# Shutdown_2019_v1_1_TractionCtl.net
KiCad netlist of a schematic drawn in Altium Designer
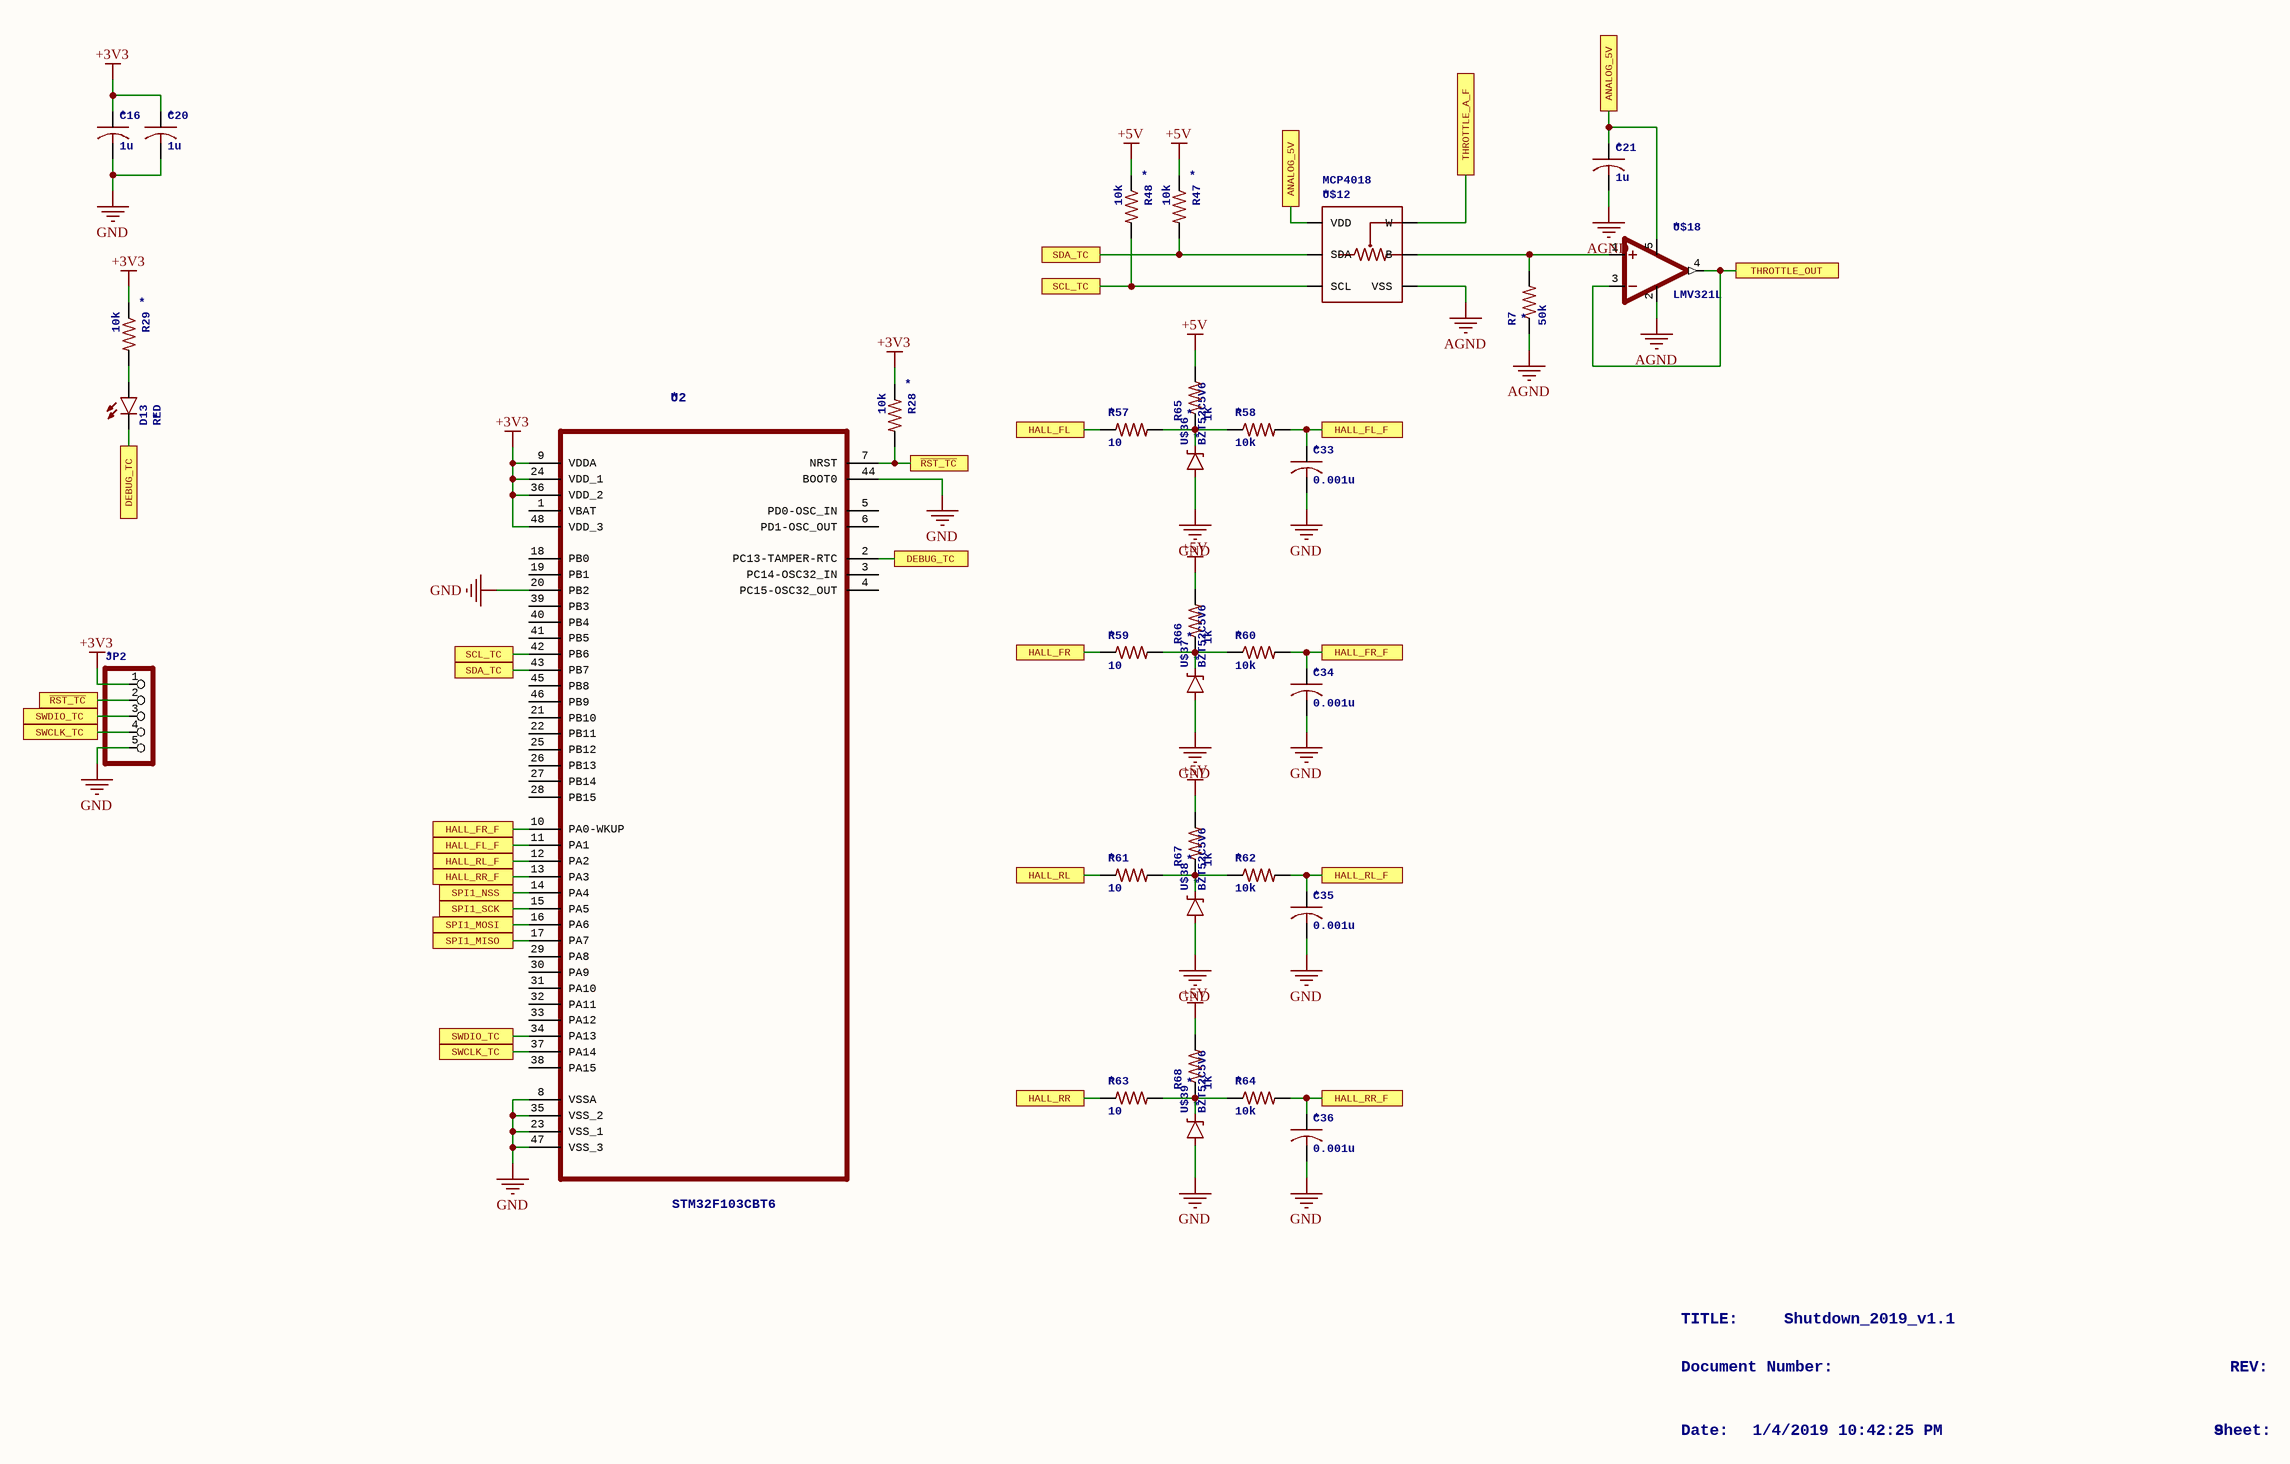
[diagram p0: Shutdown_2019_v1.1_TractionCtl.SchDoc]

(export (version "E")
  (design (tool "Eeschema 10.0.6"))
  (components
    (comp (ref "C16")
      (value "1u")
      (footprint "C0805")
      (description "CAPACITOR, American symbol")
      (fields (field (name "NAME") "*"))
      (libsource (lib "rcl") (part "C-USC0805"))
    )
    (comp (ref "C20")
      (value "1u")
      (footprint "C0805")
      (description "CAPACITOR, American symbol")
      (fields (field (name "NAME") "*"))
      (libsource (lib "rcl") (part "C-USC0805"))
    )
    (comp (ref "C21")
      (value "1u")
      (footprint "C0603")
      (description "CAPACITOR, American symbol")
      (fields (field (name "NAME") "*"))
      (libsource (lib "rcl") (part "C-USC0603"))
    )
    (comp (ref "C33")
      (value "0.001u")
      (footprint "C0805")
      (description "CAPACITOR, American symbol")
      (fields (field (name "NAME") "*"))
      (libsource (lib "rcl") (part "C-USC0805"))
    )
    (comp (ref "C34")
      (value "0.001u")
      (footprint "C0805")
      (description "CAPACITOR, American symbol")
      (fields (field (name "NAME") "*"))
      (libsource (lib "rcl") (part "C-USC0805"))
    )
    (comp (ref "C35")
      (value "0.001u")
      (footprint "C0805")
      (description "CAPACITOR, American symbol")
      (fields (field (name "NAME") "*"))
      (libsource (lib "rcl") (part "C-USC0805"))
    )
    (comp (ref "C36")
      (value "0.001u")
      (footprint "C0805")
      (description "CAPACITOR, American symbol")
      (fields (field (name "NAME") "*"))
      (libsource (lib "rcl") (part "C-USC0805"))
    )
    (comp (ref "D13")
      (value "RED")
      (footprint "LED-0603")
      (fields (field (name "NAME") "*"))
      (libsource (lib "SparkFun-LED") (part "LED-RED0603"))
    )
    (comp (ref "JP2")
      (value "PINHD-1X5")
      (footprint "1X05")
      (description "PIN HEADER")
      (fields (field (name "NAME") "*") (field (name "LIBRARYNAME") "Headers_IFE"))
      (libsource (lib "Headers_IFE") (part "PINHD-1X5"))
    )
    (comp (ref "R7")
      (value "50k")
      (footprint "R0603")
      (description "RESISTOR, American symbol")
      (fields (field (name "NAME") "*"))
      (libsource (lib "rcl") (part "R-US_R0603"))
    )
    (comp (ref "R28")
      (value "10k")
      (footprint "R0603")
      (description "RESISTOR, American symbol")
      (fields (field (name "NAME") "*"))
      (libsource (lib "rcl") (part "R-US_R0603"))
    )
    (comp (ref "R29")
      (value "10k")
      (footprint "R0603")
      (description "RESISTOR, American symbol")
      (fields (field (name "NAME") "*"))
      (libsource (lib "rcl") (part "R-US_R0603"))
    )
    (comp (ref "R47")
      (value "10k")
      (footprint "R0603")
      (description "RESISTOR, American symbol")
      (fields (field (name "NAME") "*"))
      (libsource (lib "rcl") (part "R-US_R0603"))
    )
    (comp (ref "R48")
      (value "10k")
      (footprint "R0603")
      (description "RESISTOR, American symbol")
      (fields (field (name "NAME") "*"))
      (libsource (lib "rcl") (part "R-US_R0603"))
    )
    (comp (ref "R57")
      (value "10")
      (footprint "R0603")
      (description "RESISTOR, American symbol")
      (fields (field (name "NAME") "*"))
      (libsource (lib "rcl") (part "R-US_R0603"))
    )
    (comp (ref "R58")
      (value "10k")
      (footprint "R0603")
      (description "RESISTOR, American symbol")
      (fields (field (name "NAME") "*"))
      (libsource (lib "rcl") (part "R-US_R0603"))
    )
    (comp (ref "R59")
      (value "10")
      (footprint "R0603")
      (description "RESISTOR, American symbol")
      (fields (field (name "NAME") "*"))
      (libsource (lib "rcl") (part "R-US_R0603"))
    )
    (comp (ref "R60")
      (value "10k")
      (footprint "R0603")
      (description "RESISTOR, American symbol")
      (fields (field (name "NAME") "*"))
      (libsource (lib "rcl") (part "R-US_R0603"))
    )
    (comp (ref "R61")
      (value "10")
      (footprint "R0603")
      (description "RESISTOR, American symbol")
      (fields (field (name "NAME") "*"))
      (libsource (lib "rcl") (part "R-US_R0603"))
    )
    (comp (ref "R62")
      (value "10k")
      (footprint "R0603")
      (description "RESISTOR, American symbol")
      (fields (field (name "NAME") "*"))
      (libsource (lib "rcl") (part "R-US_R0603"))
    )
    (comp (ref "R63")
      (value "10")
      (footprint "R0603")
      (description "RESISTOR, American symbol")
      (fields (field (name "NAME") "*"))
      (libsource (lib "rcl") (part "R-US_R0603"))
    )
    (comp (ref "R64")
      (value "10k")
      (footprint "R0603")
      (description "RESISTOR, American symbol")
      (fields (field (name "NAME") "*"))
      (libsource (lib "rcl") (part "R-US_R0603"))
    )
    (comp (ref "R65")
      (value "1k")
      (footprint "R0603")
      (description "RESISTOR, American symbol")
      (fields (field (name "NAME") "*"))
      (libsource (lib "rcl") (part "R-US_R0603"))
    )
    (comp (ref "R66")
      (value "1k")
      (footprint "R0603")
      (description "RESISTOR, American symbol")
      (fields (field (name "NAME") "*"))
      (libsource (lib "rcl") (part "R-US_R0603"))
    )
    (comp (ref "R67")
      (value "1k")
      (footprint "R0603")
      (description "RESISTOR, American symbol")
      (fields (field (name "NAME") "*"))
      (libsource (lib "rcl") (part "R-US_R0603"))
    )
    (comp (ref "R68")
      (value "1k")
      (footprint "R0603")
      (description "RESISTOR, American symbol")
      (fields (field (name "NAME") "*"))
      (libsource (lib "rcl") (part "R-US_R0603"))
    )
    (comp (ref "U$12")
      (value "MCP4018")
      (footprint "SOT23-6")
      (description "MICROCHIP MCP40187-Bit Single I2Câ„¢ Digital POT with Volatile Memory in SC70Datasheet")
      (fields (field (name "NAME") "*"))
      (libsource (lib "MICROCHIP") (part "MCP4018"))
    )
    (comp (ref "U$18")
      (value "LMV321L")
      (footprint "SOT23-5")
      (description "STM LMV321LRail to Rail General Purpose Op-AmpDatasheet")
      (fields (field (name "NAME") "*"))
      (libsource (lib "STM") (part "LMV321L"))
    )
    (comp (ref "U$36")
      (value "BZT52C5V6")
      (footprint "SOD-123")
      (description "DIODES INC BZT52C Small form factor Zener Diode Datasheet")
      (fields (field (name "NAME") "*"))
      (libsource (lib "DIODES_INC") (part "BZT52C"))
    )
    (comp (ref "U$37")
      (value "BZT52C5V6")
      (footprint "SOD-123")
      (description "DIODES INC BZT52C Small form factor Zener Diode Datasheet")
      (fields (field (name "NAME") "*"))
      (libsource (lib "DIODES_INC") (part "BZT52C"))
    )
    (comp (ref "U$38")
      (value "BZT52C5V6")
      (footprint "SOD-123")
      (description "DIODES INC BZT52C Small form factor Zener Diode Datasheet")
      (fields (field (name "NAME") "*"))
      (libsource (lib "DIODES_INC") (part "BZT52C"))
    )
    (comp (ref "U$39")
      (value "BZT52C5V6")
      (footprint "SOD-123")
      (description "DIODES INC BZT52C Small form factor Zener Diode Datasheet")
      (fields (field (name "NAME") "*"))
      (libsource (lib "DIODES_INC") (part "BZT52C"))
    )
    (comp (ref "U2")
      (value "STM32F103CBT6")
      (footprint "QFP50P900X900X160-48N")
      (description "Medium-density performance line ARM-based 32-bit MCU")
      (fields
        (field (name "NAME") "*")
        (field (name "LIBRARYNAME") "ST Microelctronics_By_element14_Batch_1")
      )
      (libsource (lib "ST Microelctronics_By_element14_Batch_1") (part "STM32F103CBT6"))
    )
  )
  (nets
    (net (code "1") (name "+3V3") (class "Default")
      (node (ref "C16") (pin "1") (pinfunction "1_1") (pintype "passive"))
      (node (ref "C20") (pin "1") (pinfunction "1_1") (pintype "passive"))
      (node (ref "JP2") (pin "1") (pinfunction "1_1") (pintype "passive"))
      (node (ref "R28") (pin "1") (pinfunction "1_1") (pintype "passive"))
      (node (ref "R29") (pin "1") (pinfunction "1_1") (pintype "passive"))
      (node (ref "U2") (pin "24") (pinfunction "VDD_1_24") (pintype "passive"))
      (node (ref "U2") (pin "36") (pinfunction "VDD_2_36") (pintype "power_in"))
      (node (ref "U2") (pin "48") (pinfunction "VDD_3_48") (pintype "power_in"))
      (node (ref "U2") (pin "9") (pinfunction "VDDA_9") (pintype "power_in"))
    )
    (net (code "2") (name "+5V") (class "Default")
      (node (ref "R47") (pin "1") (pinfunction "1_1") (pintype "passive"))
      (node (ref "R48") (pin "1") (pinfunction "1_1") (pintype "passive"))
      (node (ref "R65") (pin "2") (pinfunction "2_2") (pintype "passive"))
      (node (ref "R66") (pin "2") (pinfunction "2_2") (pintype "passive"))
      (node (ref "R67") (pin "2") (pinfunction "2_2") (pintype "passive"))
      (node (ref "R68") (pin "2") (pinfunction "2_2") (pintype "passive"))
    )
    (net (code "3") (name "/ANALOG_5V") (class "Default")
      (node (ref "C21") (pin "1") (pinfunction "1_1") (pintype "passive"))
      (node (ref "U$12") (pin "1") (pinfunction "VDD_1") (pintype "passive"))
      (node (ref "U$18") (pin "5") (pinfunction "VDD_5") (pintype "passive"))
    )
    (net (code "4") (name "/DEBUG_TC") (class "Default")
      (node (ref "D13") (pin "C") (pinfunction "C_C") (pintype "passive"))
      (node (ref "U2") (pin "2") (pinfunction "PC13-TAMPER-RTC_2") (pintype "passive"))
    )
    (net (code "5") (name "/HALL_FL") (class "Default")
      (node (ref "R57") (pin "1") (pinfunction "1_1") (pintype "passive"))
    )
    (net (code "6") (name "/HALL_FL_F") (class "Default")
      (node (ref "C33") (pin "1") (pinfunction "1_1") (pintype "passive"))
      (node (ref "R58") (pin "2") (pinfunction "2_2") (pintype "passive"))
      (node (ref "U2") (pin "11") (pinfunction "PA1_11") (pintype "passive"))
    )
    (net (code "7") (name "/HALL_FR") (class "Default")
      (node (ref "R59") (pin "1") (pinfunction "1_1") (pintype "passive"))
    )
    (net (code "8") (name "/HALL_FR_F") (class "Default")
      (node (ref "C34") (pin "1") (pinfunction "1_1") (pintype "passive"))
      (node (ref "R60") (pin "2") (pinfunction "2_2") (pintype "passive"))
      (node (ref "U2") (pin "10") (pinfunction "PA0-WKUP_10") (pintype "passive"))
    )
    (net (code "9") (name "/HALL_RL") (class "Default")
      (node (ref "R61") (pin "1") (pinfunction "1_1") (pintype "passive"))
    )
    (net (code "10") (name "/HALL_RL_F") (class "Default")
      (node (ref "C35") (pin "1") (pinfunction "1_1") (pintype "passive"))
      (node (ref "R62") (pin "2") (pinfunction "2_2") (pintype "passive"))
      (node (ref "U2") (pin "12") (pinfunction "PA2_12") (pintype "passive"))
    )
    (net (code "11") (name "/HALL_RR") (class "Default")
      (node (ref "R63") (pin "1") (pinfunction "1_1") (pintype "passive"))
    )
    (net (code "12") (name "/HALL_RR_F") (class "Default")
      (node (ref "C36") (pin "1") (pinfunction "1_1") (pintype "passive"))
      (node (ref "R64") (pin "2") (pinfunction "2_2") (pintype "passive"))
      (node (ref "U2") (pin "13") (pinfunction "PA3_13") (pintype "passive"))
    )
    (net (code "13") (name "/SCL_TC") (class "Default")
      (node (ref "R48") (pin "2") (pinfunction "2_2") (pintype "passive"))
      (node (ref "U$12") (pin "3") (pinfunction "SCL_3") (pintype "passive"))
      (node (ref "U2") (pin "42") (pinfunction "PB6_42") (pintype "passive"))
    )
    (net (code "14") (name "/SDA_TC") (class "Default")
      (node (ref "R47") (pin "2") (pinfunction "2_2") (pintype "passive"))
      (node (ref "U$12") (pin "4") (pinfunction "SDA_4") (pintype "passive"))
      (node (ref "U2") (pin "43") (pinfunction "PB7_43") (pintype "passive"))
    )
    (net (code "15") (name "/SPI1_MISO") (class "Default")
      (node (ref "U2") (pin "17") (pinfunction "PA7_17") (pintype "passive"))
    )
    (net (code "16") (name "/SPI1_MOSI") (class "Default")
      (node (ref "U2") (pin "16") (pinfunction "PA6_16") (pintype "passive"))
    )
    (net (code "17") (name "/SPI1_NSS") (class "Default")
      (node (ref "U2") (pin "14") (pinfunction "PA4_14") (pintype "passive"))
    )
    (net (code "18") (name "/SPI1_SCK") (class "Default")
      (node (ref "U2") (pin "15") (pinfunction "PA5_15") (pintype "passive"))
    )
    (net (code "19") (name "/SWCLK_TC") (class "Default")
      (node (ref "JP2") (pin "4") (pinfunction "4_4") (pintype "passive"))
      (node (ref "U2") (pin "37") (pinfunction "PA14_37") (pintype "passive"))
    )
    (net (code "20") (name "/SWDIO_TC") (class "Default")
      (node (ref "JP2") (pin "3") (pinfunction "3_3") (pintype "passive"))
      (node (ref "U2") (pin "34") (pinfunction "PA13_34") (pintype "passive"))
    )
    (net (code "21") (name "/THROTTLE_A_F") (class "Default")
      (node (ref "U$12") (pin "6") (pinfunction "W_6") (pintype "passive"))
    )
    (net (code "22") (name "/THROTTLE_OUT") (class "Default")
      (node (ref "U$18") (pin "3") (pinfunction "-IN_3") (pintype "passive"))
      (node (ref "U$18") (pin "4") (pinfunction "OUT_4") (pintype "output"))
    )
    (net (code "23") (name "/~{RST_TC}") (class "Default")
      (node (ref "JP2") (pin "2") (pinfunction "2_2") (pintype "passive"))
      (node (ref "R28") (pin "2") (pinfunction "2_2") (pintype "passive"))
      (node (ref "U2") (pin "7") (pinfunction "NRST_7") (pintype "passive"))
    )
    (net (code "24") (name "AGND") (class "Default")
      (node (ref "C21") (pin "2") (pinfunction "2_2") (pintype "passive"))
      (node (ref "R7") (pin "1") (pinfunction "1_1") (pintype "passive"))
      (node (ref "U$12") (pin "2") (pinfunction "VSS_2") (pintype "passive"))
      (node (ref "U$18") (pin "2") (pinfunction "GND_2") (pintype "passive"))
    )
    (net (code "25") (name "GND") (class "Default")
      (node (ref "C16") (pin "2") (pinfunction "2_2") (pintype "passive"))
      (node (ref "C20") (pin "2") (pinfunction "2_2") (pintype "passive"))
      (node (ref "C33") (pin "2") (pinfunction "2_2") (pintype "passive"))
      (node (ref "C34") (pin "2") (pinfunction "2_2") (pintype "passive"))
      (node (ref "C35") (pin "2") (pinfunction "2_2") (pintype "passive"))
      (node (ref "C36") (pin "2") (pinfunction "2_2") (pintype "passive"))
      (node (ref "JP2") (pin "5") (pinfunction "5_5") (pintype "passive"))
      (node (ref "U$36") (pin "A") (pinfunction "A_A") (pintype "passive"))
      (node (ref "U$37") (pin "A") (pinfunction "A_A") (pintype "passive"))
      (node (ref "U$38") (pin "A") (pinfunction "A_A") (pintype "passive"))
      (node (ref "U$39") (pin "A") (pinfunction "A_A") (pintype "passive"))
      (node (ref "U2") (pin "20") (pinfunction "PB2_20") (pintype "passive"))
      (node (ref "U2") (pin "23") (pinfunction "VSS_1_23") (pintype "passive"))
      (node (ref "U2") (pin "35") (pinfunction "VSS_2_35") (pintype "passive"))
      (node (ref "U2") (pin "44") (pinfunction "BOOT0_44") (pintype "passive"))
      (node (ref "U2") (pin "47") (pinfunction "VSS_3_47") (pintype "passive"))
      (node (ref "U2") (pin "8") (pinfunction "VSSA_8") (pintype "passive"))
    )
    (net (code "26") (name "Net-(D13-PadA)") (class "Default")
      (node (ref "D13") (pin "A") (pinfunction "A_A") (pintype "passive"))
      (node (ref "R29") (pin "2") (pinfunction "2_2") (pintype "passive"))
    )
    (net (code "27") (name "Net-(R57-Pad2)") (class "Default")
      (node (ref "R57") (pin "2") (pinfunction "2_2") (pintype "passive"))
      (node (ref "R58") (pin "1") (pinfunction "1_1") (pintype "passive"))
      (node (ref "R65") (pin "1") (pinfunction "1_1") (pintype "passive"))
      (node (ref "U$36") (pin "C") (pinfunction "C_C") (pintype "passive"))
    )
    (net (code "28") (name "Net-(R59-Pad2)") (class "Default")
      (node (ref "R59") (pin "2") (pinfunction "2_2") (pintype "passive"))
      (node (ref "R60") (pin "1") (pinfunction "1_1") (pintype "passive"))
      (node (ref "R66") (pin "1") (pinfunction "1_1") (pintype "passive"))
      (node (ref "U$37") (pin "C") (pinfunction "C_C") (pintype "passive"))
    )
    (net (code "29") (name "Net-(R61-Pad2)") (class "Default")
      (node (ref "R61") (pin "2") (pinfunction "2_2") (pintype "passive"))
      (node (ref "R62") (pin "1") (pinfunction "1_1") (pintype "passive"))
      (node (ref "R67") (pin "1") (pinfunction "1_1") (pintype "passive"))
      (node (ref "U$38") (pin "C") (pinfunction "C_C") (pintype "passive"))
    )
    (net (code "30") (name "Net-(R63-Pad2)") (class "Default")
      (node (ref "R63") (pin "2") (pinfunction "2_2") (pintype "passive"))
      (node (ref "R64") (pin "1") (pinfunction "1_1") (pintype "passive"))
      (node (ref "R68") (pin "1") (pinfunction "1_1") (pintype "passive"))
      (node (ref "U$39") (pin "C") (pinfunction "C_C") (pintype "passive"))
    )
    (net (code "31") (name "Net-(U$12-B)") (class "Default")
      (node (ref "R7") (pin "2") (pinfunction "2_2") (pintype "passive"))
      (node (ref "U$12") (pin "5") (pinfunction "B_5") (pintype "passive"))
      (node (ref "U$18") (pin "1") (pinfunction "+IN_1") (pintype "passive"))
    )
    (net (code "32") (name "unconnected-(U2-PA8-Pad29)") (class "Default")
      (node (ref "U2") (pin "29") (pinfunction "PA8_29") (pintype "passive"))
    )
    (net (code "33") (name "unconnected-(U2-PA9-Pad30)") (class "Default")
      (node (ref "U2") (pin "30") (pinfunction "PA9_30") (pintype "passive"))
    )
    (net (code "34") (name "unconnected-(U2-PA10-Pad31)") (class "Default")
      (node (ref "U2") (pin "31") (pinfunction "PA10_31") (pintype "passive"))
    )
    (net (code "35") (name "unconnected-(U2-PA11-Pad32)") (class "Default")
      (node (ref "U2") (pin "32") (pinfunction "PA11_32") (pintype "power_in"))
    )
    (net (code "36") (name "unconnected-(U2-PA12-Pad33)") (class "Default")
      (node (ref "U2") (pin "33") (pinfunction "PA12_33") (pintype "passive"))
    )
    (net (code "37") (name "unconnected-(U2-PA15-Pad38)") (class "Default")
      (node (ref "U2") (pin "38") (pinfunction "PA15_38") (pintype "passive"))
    )
    (net (code "38") (name "unconnected-(U2-PB0-Pad18)") (class "Default")
      (node (ref "U2") (pin "18") (pinfunction "PB0_18") (pintype "passive"))
    )
    (net (code "39") (name "unconnected-(U2-PB1-Pad19)") (class "Default")
      (node (ref "U2") (pin "19") (pinfunction "PB1_19") (pintype "passive"))
    )
    (net (code "40") (name "unconnected-(U2-PB3-Pad39)") (class "Default")
      (node (ref "U2") (pin "39") (pinfunction "PB3_39") (pintype "passive"))
    )
    (net (code "41") (name "unconnected-(U2-PB4-Pad40)") (class "Default")
      (node (ref "U2") (pin "40") (pinfunction "PB4_40") (pintype "passive"))
    )
    (net (code "42") (name "unconnected-(U2-PB5-Pad41)") (class "Default")
      (node (ref "U2") (pin "41") (pinfunction "PB5_41") (pintype "passive"))
    )
    (net (code "43") (name "unconnected-(U2-PB8-Pad45)") (class "Default")
      (node (ref "U2") (pin "45") (pinfunction "PB8_45") (pintype "passive"))
    )
    (net (code "44") (name "unconnected-(U2-PB9-Pad46)") (class "Default")
      (node (ref "U2") (pin "46") (pinfunction "PB9_46") (pintype "passive"))
    )
    (net (code "45") (name "unconnected-(U2-PB10-Pad21)") (class "Default")
      (node (ref "U2") (pin "21") (pinfunction "PB10_21") (pintype "passive"))
    )
    (net (code "46") (name "unconnected-(U2-PB11-Pad22)") (class "Default")
      (node (ref "U2") (pin "22") (pinfunction "PB11_22") (pintype "passive"))
    )
    (net (code "47") (name "unconnected-(U2-PB12-Pad25)") (class "Default")
      (node (ref "U2") (pin "25") (pinfunction "PB12_25") (pintype "passive"))
    )
    (net (code "48") (name "unconnected-(U2-PB13-Pad26)") (class "Default")
      (node (ref "U2") (pin "26") (pinfunction "PB13_26") (pintype "passive"))
    )
    (net (code "49") (name "unconnected-(U2-PB14-Pad27)") (class "Default")
      (node (ref "U2") (pin "27") (pinfunction "PB14_27") (pintype "passive"))
    )
    (net (code "50") (name "unconnected-(U2-PB15-Pad28)") (class "Default")
      (node (ref "U2") (pin "28") (pinfunction "PB15_28") (pintype "passive"))
    )
    (net (code "51") (name "unconnected-(U2-PC14-OSC32_IN-Pad3)") (class "Default")
      (node (ref "U2") (pin "3") (pinfunction "PC14-OSC32_IN_3") (pintype "passive"))
    )
    (net (code "52") (name "unconnected-(U2-PC15-OSC32_OUT-Pad4)") (class "Default")
      (node (ref "U2") (pin "4") (pinfunction "PC15-OSC32_OUT_4") (pintype "passive"))
    )
    (net (code "53") (name "unconnected-(U2-PD0-OSC_IN-Pad5)") (class "Default")
      (node (ref "U2") (pin "5") (pinfunction "PD0-OSC_IN_5") (pintype "passive"))
    )
    (net (code "54") (name "unconnected-(U2-PD1-OSC_OUT-Pad6)") (class "Default")
      (node (ref "U2") (pin "6") (pinfunction "PD1-OSC_OUT_6") (pintype "passive"))
    )
    (net (code "55") (name "unconnected-(U2-VBAT-Pad1)") (class "Default")
      (node (ref "U2") (pin "1") (pinfunction "VBAT_1") (pintype "passive"))
    )
  )
)
